# BigLatchingRelayOnAStick-Electron.net
KiCad netlist of a schematic drawn in EAGLE
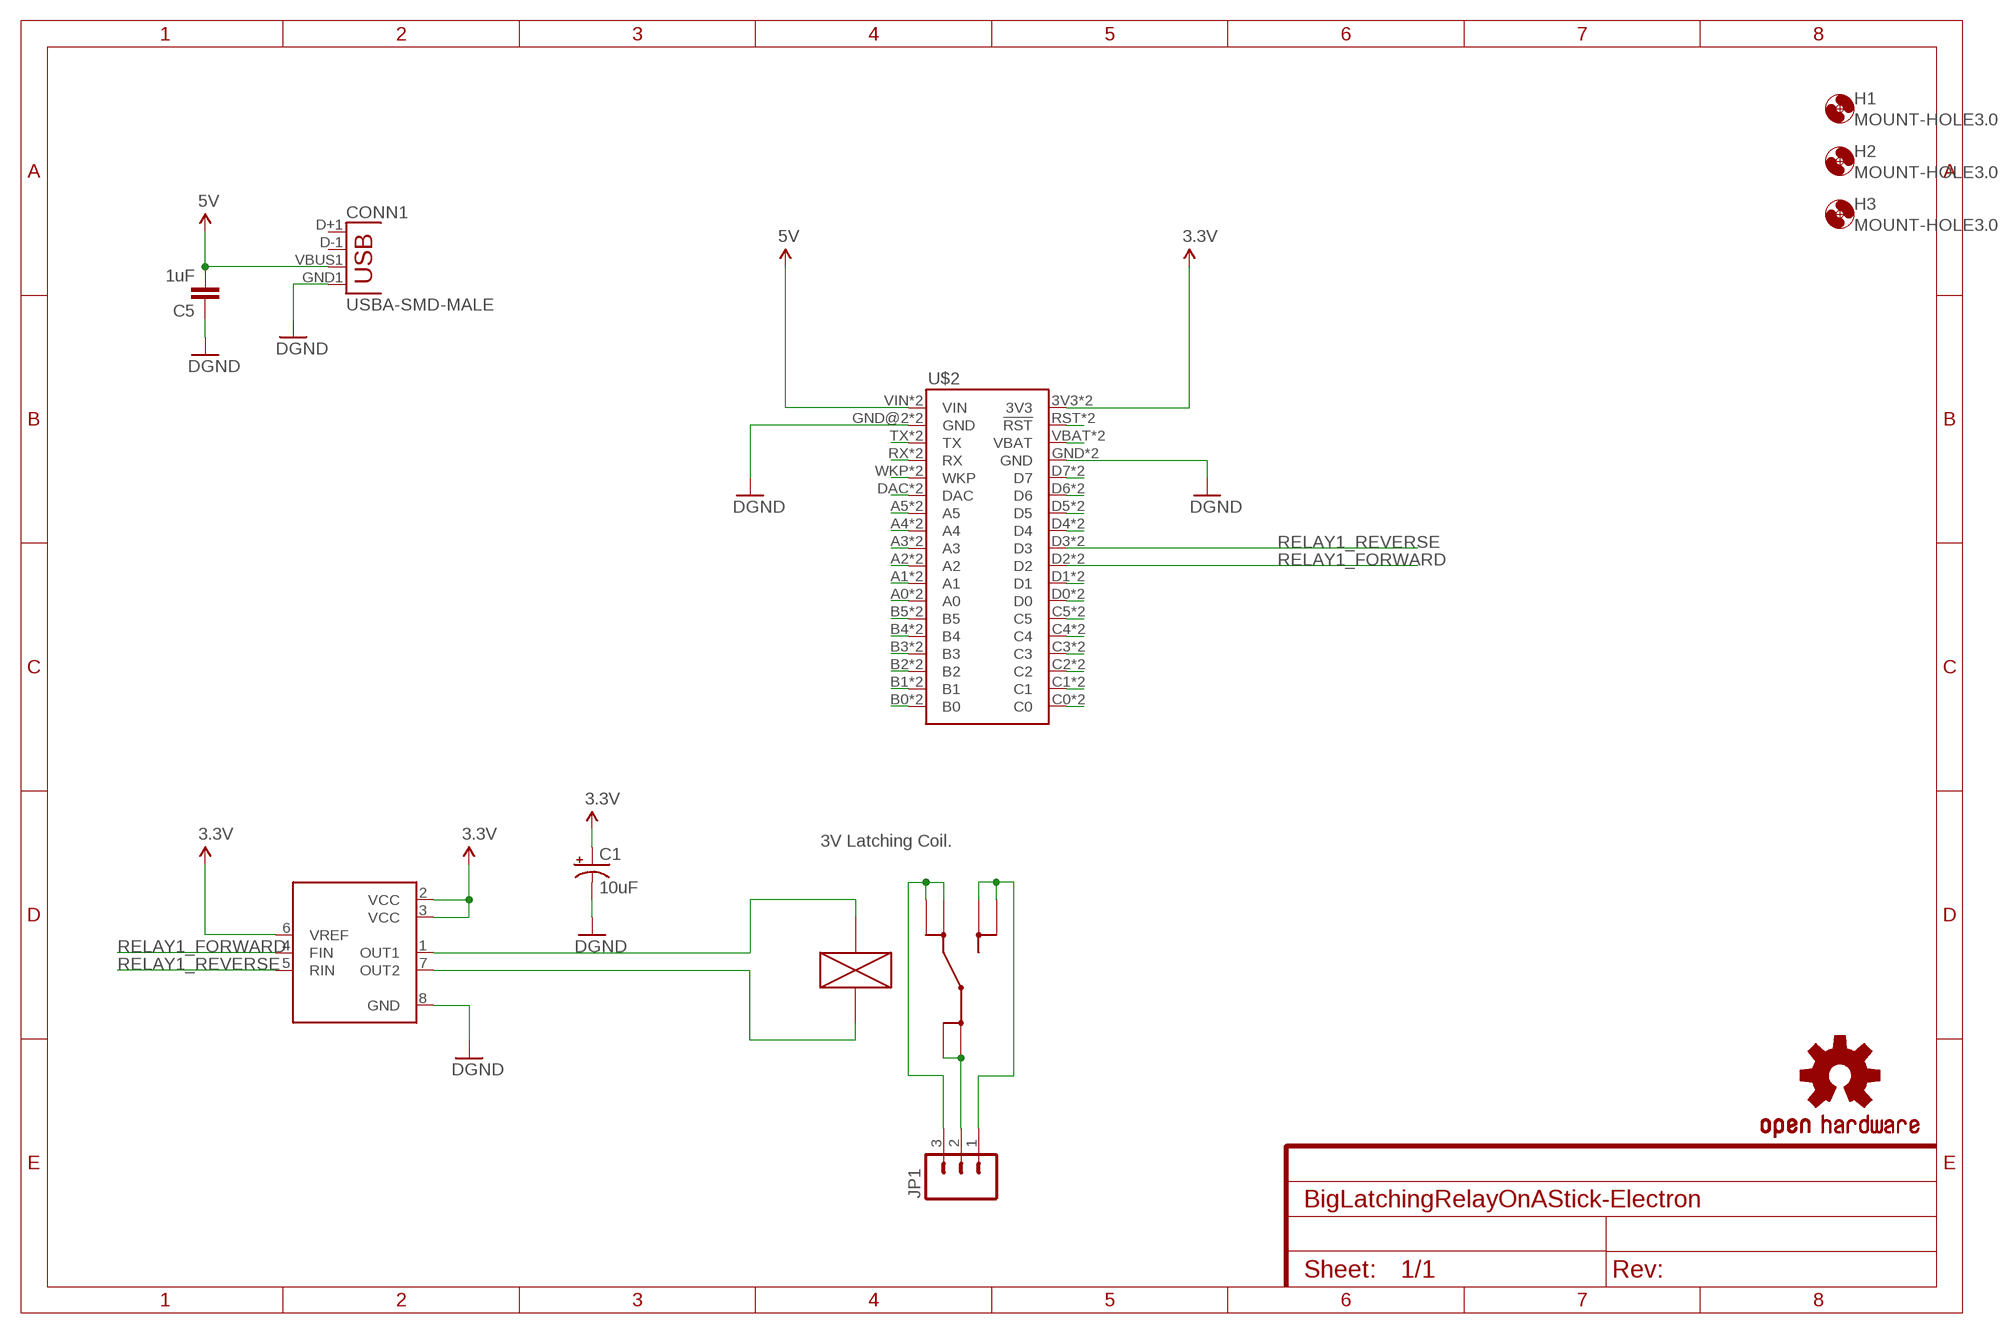
[diagram p0: schematic, sheet 1]

(export (version "E")
  (design (tool "Eeschema 10.0.6"))
  (components
    (comp (ref "C1")
      (value "10uF")
      (footprint "eagle-import:EIA3216")
      (libsource (lib "eagle-import") (part "10UF-16V-10%(TANT)"))
    )
    (comp (ref "C5")
      (value "1uF")
      (footprint "eagle-import:0805")
      (libsource (lib "eagle-import") (part "CAP0805"))
    )
    (comp (ref "CONN1")
      (value "USBA-SMD-MALE")
      (footprint "eagle-import:USB-A-SMT-MALE")
      (libsource (lib "eagle-import") (part "USBA-SMD-MALE"))
    )
    (comp (ref "H1")
      (value "MOUNT-HOLE3.0")
      (footprint "eagle-import:3,0")
      (libsource (lib "eagle-import") (part "MOUNT-HOLE3.0"))
    )
    (comp (ref "H2")
      (value "MOUNT-HOLE3.0")
      (footprint "eagle-import:3,0")
      (libsource (lib "eagle-import") (part "MOUNT-HOLE3.0"))
    )
    (comp (ref "H3")
      (value "MOUNT-HOLE3.0")
      (footprint "eagle-import:3,0")
      (libsource (lib "eagle-import") (part "MOUNT-HOLE3.0"))
    )
    (comp (ref "IC2")
      (value "BD6211F")
      (footprint "eagle-import:SOP8")
      (libsource (lib "eagle-import") (part "BD6211F"))
    )
    (comp (ref "JP1")
      (value "M03-SCREW-5MM")
      (footprint "eagle-import:SCREWTERMINAL-5MM-3")
      (libsource (lib "eagle-import") (part "M03-SCREW-5MM"))
    )
    (comp (ref "LOGO2")
      (value "OSHW-LOGOS")
      (footprint "eagle-import:OSHW-LOGO-S")
      (libsource (lib "eagle-import") (part "OSHW-LOGOS"))
    )
    (comp (ref "U$1")
      (value "RELAY_G5RL-1E")
      (footprint "eagle-import:G5RL-1E")
      (libsource (lib "eagle-import") (part "RELAY_G5RL-1E"))
    )
    (comp (ref "U$2")
      (value "ELECTRONDUALNAMED")
      (footprint "eagle-import:ELECTRON_SIMPLE_SILK_NAMES_DUAL")
      (libsource (lib "eagle-import") (part "ELECTRONDUALNAMED"))
    )
  )
  (nets
    (net (code "1") (name "/RELAY1_FORWARD") (class "Default")
      (node (ref "IC2") (pin "4") (pinfunction "FIN_4") (pintype "input"))
      (node (ref "U$2") (pin "D2") (pinfunction "D2_D2") (pintype "bidirectional"))
      (node (ref "U$2") (pin "D2_1") (pinfunction "D2_D2_1") (pintype "bidirectional"))
    )
    (net (code "2") (name "/RELAY1_REVERSE") (class "Default")
      (node (ref "IC2") (pin "5") (pinfunction "RIN_5") (pintype "input"))
      (node (ref "U$2") (pin "D3") (pinfunction "D3_D3") (pintype "bidirectional"))
      (node (ref "U$2") (pin "D3_1") (pinfunction "D3_D3_1") (pintype "bidirectional"))
    )
    (net (code "3") (name "3.3V") (class "Default")
      (node (ref "C1") (pin "A") (pinfunction "+_A") (pintype "passive"))
      (node (ref "IC2") (pin "2") (pinfunction "VCC_2") (pintype "power_in"))
      (node (ref "IC2") (pin "3") (pinfunction "VCC_3") (pintype "power_in"))
      (node (ref "IC2") (pin "6") (pinfunction "VREF_6") (pintype "passive"))
      (node (ref "U$2") (pin "3V3") (pinfunction "3V3_3V3") (pintype "power_in"))
      (node (ref "U$2") (pin "3V3_1") (pinfunction "3V3_3V3_1") (pintype "power_in"))
    )
    (net (code "4") (name "5V") (class "Default")
      (node (ref "C5") (pin "2") (pinfunction "2_2") (pintype "passive"))
      (node (ref "CONN1") (pin "VBUS1") (pinfunction "VBUS_VBUS1") (pintype "bidirectional"))
      (node (ref "U$2") (pin "VIN") (pinfunction "VIN_VIN") (pintype "power_in"))
      (node (ref "U$2") (pin "VIN_1B") (pinfunction "VIN_VIN_1B") (pintype "power_in"))
    )
    (net (code "5") (name "DGND") (class "Default")
      (node (ref "C1") (pin "C") (pinfunction "-_C") (pintype "passive"))
      (node (ref "C5") (pin "1") (pinfunction "1_1") (pintype "passive"))
      (node (ref "CONN1") (pin "GND1") (pinfunction "GND_GND1") (pintype "bidirectional"))
      (node (ref "IC2") (pin "8") (pinfunction "GND_8") (pintype "power_in"))
      (node (ref "U$2") (pin "GND") (pinfunction "GND_GND") (pintype "power_in"))
      (node (ref "U$2") (pin "GND@2") (pinfunction "GND_GND@2") (pintype "power_in"))
      (node (ref "U$2") (pin "GND_1") (pinfunction "GND_GND_1") (pintype "power_in"))
      (node (ref "U$2") (pin "GND_1B") (pinfunction "GND_GND_1B") (pintype "power_in"))
    )
    (net (code "6") (name "Net-(IC2-OUT1)") (class "Default")
      (node (ref "IC2") (pin "1") (pinfunction "OUT1_1") (pintype "output"))
      (node (ref "U$1") (pin "COIL+") (pinfunction "COIL+_COIL+") (pintype "bidirectional"))
    )
    (net (code "7") (name "Net-(IC2-OUT2)") (class "Default")
      (node (ref "IC2") (pin "7") (pinfunction "OUT2_7") (pintype "output"))
      (node (ref "U$1") (pin "COIL-") (pinfunction "COIL-_COIL-") (pintype "bidirectional"))
    )
    (net (code "8") (name "Net-(JP1-Pad1)") (class "Default")
      (node (ref "JP1") (pin "1") (pinfunction "1_1") (pintype "passive"))
      (node (ref "U$1") (pin "NO@1") (pinfunction "NO_NO@1") (pintype "bidirectional"))
      (node (ref "U$1") (pin "NO@2") (pinfunction "NO_NO@2") (pintype "bidirectional"))
    )
    (net (code "9") (name "Net-(JP1-Pad2)") (class "Default")
      (node (ref "JP1") (pin "2") (pinfunction "2_2") (pintype "passive"))
      (node (ref "U$1") (pin "COM@1") (pinfunction "COM_COM@1") (pintype "bidirectional"))
      (node (ref "U$1") (pin "COM@2") (pinfunction "COM_COM@2") (pintype "bidirectional"))
    )
    (net (code "10") (name "Net-(JP1-Pad3)") (class "Default")
      (node (ref "JP1") (pin "3") (pinfunction "3_3") (pintype "passive"))
      (node (ref "U$1") (pin "NC@1") (pinfunction "NC_NC@1") (pintype "bidirectional"))
      (node (ref "U$1") (pin "NC@2") (pinfunction "NC_NC@2") (pintype "bidirectional"))
    )
    (net (code "11") (name "Net-(U$2-A0-PadA0_1)") (class "Default")
      (node (ref "U$2") (pin "A0") (pinfunction "A0_A0") (pintype "bidirectional"))
      (node (ref "U$2") (pin "A0_1") (pinfunction "A0_A0_1") (pintype "bidirectional"))
    )
    (net (code "12") (name "Net-(U$2-A1-PadA1_1)") (class "Default")
      (node (ref "U$2") (pin "A1") (pinfunction "A1_A1") (pintype "bidirectional"))
      (node (ref "U$2") (pin "A1_1") (pinfunction "A1_A1_1") (pintype "bidirectional"))
    )
    (net (code "13") (name "Net-(U$2-A2-PadA2_1)") (class "Default")
      (node (ref "U$2") (pin "A2") (pinfunction "A2_A2") (pintype "bidirectional"))
      (node (ref "U$2") (pin "A2_1") (pinfunction "A2_A2_1") (pintype "bidirectional"))
    )
    (net (code "14") (name "Net-(U$2-A3-PadA3_1)") (class "Default")
      (node (ref "U$2") (pin "A3") (pinfunction "A3_A3") (pintype "bidirectional"))
      (node (ref "U$2") (pin "A3_1") (pinfunction "A3_A3_1") (pintype "bidirectional"))
    )
    (net (code "15") (name "Net-(U$2-A4-PadA4_1)") (class "Default")
      (node (ref "U$2") (pin "A4") (pinfunction "A4_A4") (pintype "bidirectional"))
      (node (ref "U$2") (pin "A4_1") (pinfunction "A4_A4_1") (pintype "bidirectional"))
    )
    (net (code "16") (name "Net-(U$2-A5-PadA5_1)") (class "Default")
      (node (ref "U$2") (pin "A5") (pinfunction "A5_A5") (pintype "bidirectional"))
      (node (ref "U$2") (pin "A5_1") (pinfunction "A5_A5_1") (pintype "bidirectional"))
    )
    (net (code "17") (name "Net-(U$2-B0-PadB0_1)") (class "Default")
      (node (ref "U$2") (pin "B0") (pinfunction "B0_B0") (pintype "bidirectional"))
      (node (ref "U$2") (pin "B0_1") (pinfunction "B0_B0_1") (pintype "bidirectional"))
    )
    (net (code "18") (name "Net-(U$2-B1-PadB1_1)") (class "Default")
      (node (ref "U$2") (pin "B1") (pinfunction "B1_B1") (pintype "bidirectional"))
      (node (ref "U$2") (pin "B1_1") (pinfunction "B1_B1_1") (pintype "bidirectional"))
    )
    (net (code "19") (name "Net-(U$2-B2-PadB2_1)") (class "Default")
      (node (ref "U$2") (pin "B2") (pinfunction "B2_B2") (pintype "bidirectional"))
      (node (ref "U$2") (pin "B2_1") (pinfunction "B2_B2_1") (pintype "bidirectional"))
    )
    (net (code "20") (name "Net-(U$2-B3-PadB3_1)") (class "Default")
      (node (ref "U$2") (pin "B3") (pinfunction "B3_B3") (pintype "bidirectional"))
      (node (ref "U$2") (pin "B3_1") (pinfunction "B3_B3_1") (pintype "bidirectional"))
    )
    (net (code "21") (name "Net-(U$2-B4-PadB4_1)") (class "Default")
      (node (ref "U$2") (pin "B4") (pinfunction "B4_B4") (pintype "bidirectional"))
      (node (ref "U$2") (pin "B4_1") (pinfunction "B4_B4_1") (pintype "bidirectional"))
    )
    (net (code "22") (name "Net-(U$2-B5-PadB5_1)") (class "Default")
      (node (ref "U$2") (pin "B5") (pinfunction "B5_B5") (pintype "bidirectional"))
      (node (ref "U$2") (pin "B5_1") (pinfunction "B5_B5_1") (pintype "bidirectional"))
    )
    (net (code "23") (name "Net-(U$2-C0-PadC0_1)") (class "Default")
      (node (ref "U$2") (pin "C0") (pinfunction "C0_C0") (pintype "bidirectional"))
      (node (ref "U$2") (pin "C0_1") (pinfunction "C0_C0_1") (pintype "bidirectional"))
    )
    (net (code "24") (name "Net-(U$2-C1-PadC1_1)") (class "Default")
      (node (ref "U$2") (pin "C1") (pinfunction "C1_C1") (pintype "bidirectional"))
      (node (ref "U$2") (pin "C1_1") (pinfunction "C1_C1_1") (pintype "bidirectional"))
    )
    (net (code "25") (name "Net-(U$2-C2-PadC2_1)") (class "Default")
      (node (ref "U$2") (pin "C2") (pinfunction "C2_C2") (pintype "bidirectional"))
      (node (ref "U$2") (pin "C2_1") (pinfunction "C2_C2_1") (pintype "bidirectional"))
    )
    (net (code "26") (name "Net-(U$2-C3-PadC3_1)") (class "Default")
      (node (ref "U$2") (pin "C3") (pinfunction "C3_C3") (pintype "bidirectional"))
      (node (ref "U$2") (pin "C3_1") (pinfunction "C3_C3_1") (pintype "bidirectional"))
    )
    (net (code "27") (name "Net-(U$2-C4-PadC4_1)") (class "Default")
      (node (ref "U$2") (pin "C4") (pinfunction "C4_C4") (pintype "bidirectional"))
      (node (ref "U$2") (pin "C4_1") (pinfunction "C4_C4_1") (pintype "bidirectional"))
    )
    (net (code "28") (name "Net-(U$2-C5-PadC5_1)") (class "Default")
      (node (ref "U$2") (pin "C5") (pinfunction "C5_C5") (pintype "bidirectional"))
      (node (ref "U$2") (pin "C5_1") (pinfunction "C5_C5_1") (pintype "bidirectional"))
    )
    (net (code "29") (name "Net-(U$2-D0-PadD0_1)") (class "Default")
      (node (ref "U$2") (pin "D0") (pinfunction "D0_D0") (pintype "bidirectional"))
      (node (ref "U$2") (pin "D0_1") (pinfunction "D0_D0_1") (pintype "bidirectional"))
    )
    (net (code "30") (name "Net-(U$2-D1-PadD1_1)") (class "Default")
      (node (ref "U$2") (pin "D1") (pinfunction "D1_D1") (pintype "bidirectional"))
      (node (ref "U$2") (pin "D1_1") (pinfunction "D1_D1_1") (pintype "bidirectional"))
    )
    (net (code "31") (name "Net-(U$2-D4-PadD4_1)") (class "Default")
      (node (ref "U$2") (pin "D4") (pinfunction "D4_D4") (pintype "bidirectional"))
      (node (ref "U$2") (pin "D4_1") (pinfunction "D4_D4_1") (pintype "bidirectional"))
    )
    (net (code "32") (name "Net-(U$2-D5-PadD5_1)") (class "Default")
      (node (ref "U$2") (pin "D5") (pinfunction "D5_D5") (pintype "bidirectional"))
      (node (ref "U$2") (pin "D5_1") (pinfunction "D5_D5_1") (pintype "bidirectional"))
    )
    (net (code "33") (name "Net-(U$2-D6-PadD6_1)") (class "Default")
      (node (ref "U$2") (pin "D6") (pinfunction "D6_D6") (pintype "bidirectional"))
      (node (ref "U$2") (pin "D6_1") (pinfunction "D6_D6_1") (pintype "bidirectional"))
    )
    (net (code "34") (name "Net-(U$2-D7-PadD7_1)") (class "Default")
      (node (ref "U$2") (pin "D7") (pinfunction "D7_D7") (pintype "bidirectional"))
      (node (ref "U$2") (pin "D7_1") (pinfunction "D7_D7_1") (pintype "bidirectional"))
    )
    (net (code "35") (name "Net-(U$2-DAC-PadDAC_1)") (class "Default")
      (node (ref "U$2") (pin "DAC") (pinfunction "DAC_DAC") (pintype "bidirectional"))
      (node (ref "U$2") (pin "DAC_1") (pinfunction "DAC_DAC_1") (pintype "bidirectional"))
    )
    (net (code "36") (name "Net-(U$2-PadRX)") (class "Default")
      (node (ref "U$2") (pin "RX") (pinfunction "RX_RX") (pintype "bidirectional"))
      (node (ref "U$2") (pin "RX_1") (pinfunction "RX_RX_1") (pintype "bidirectional"))
    )
    (net (code "37") (name "Net-(U$2-PadTX)") (class "Default")
      (node (ref "U$2") (pin "TX") (pinfunction "TX_TX") (pintype "bidirectional"))
      (node (ref "U$2") (pin "TX_1") (pinfunction "TX_TX_1") (pintype "bidirectional"))
    )
    (net (code "38") (name "Net-(U$2-PadVBAT)") (class "Default")
      (node (ref "U$2") (pin "VBAT") (pinfunction "VBAT_VBAT") (pintype "passive"))
      (node (ref "U$2") (pin "VBATT_1") (pinfunction "VBAT_VBATT_1") (pintype "passive"))
    )
    (net (code "39") (name "Net-(U$2-PadWKP)") (class "Default")
      (node (ref "U$2") (pin "WKP") (pinfunction "WKP_WKP") (pintype "bidirectional"))
      (node (ref "U$2") (pin "WKP_1") (pinfunction "WKP_WKP_1") (pintype "bidirectional"))
    )
    (net (code "40") (name "Net-(U$2-~{RST}-PadRST)") (class "Default")
      (node (ref "U$2") (pin "RST") (pinfunction "~{RST}_RST") (pintype "bidirectional"))
      (node (ref "U$2") (pin "RST_1") (pinfunction "~{RST}_RST_1") (pintype "bidirectional"))
    )
    (net (code "41") (name "unconnected-(CONN1-D+-PadD+1)") (class "Default")
      (node (ref "CONN1") (pin "D+1") (pinfunction "D+_D+1") (pintype "bidirectional"))
    )
    (net (code "42") (name "unconnected-(CONN1-D--PadD-1)") (class "Default")
      (node (ref "CONN1") (pin "D-1") (pinfunction "D-_D-1") (pintype "bidirectional"))
    )
  )
)
